# mindbrain_schematic_v2.net
KiCad netlist of a schematic drawn in EAGLE
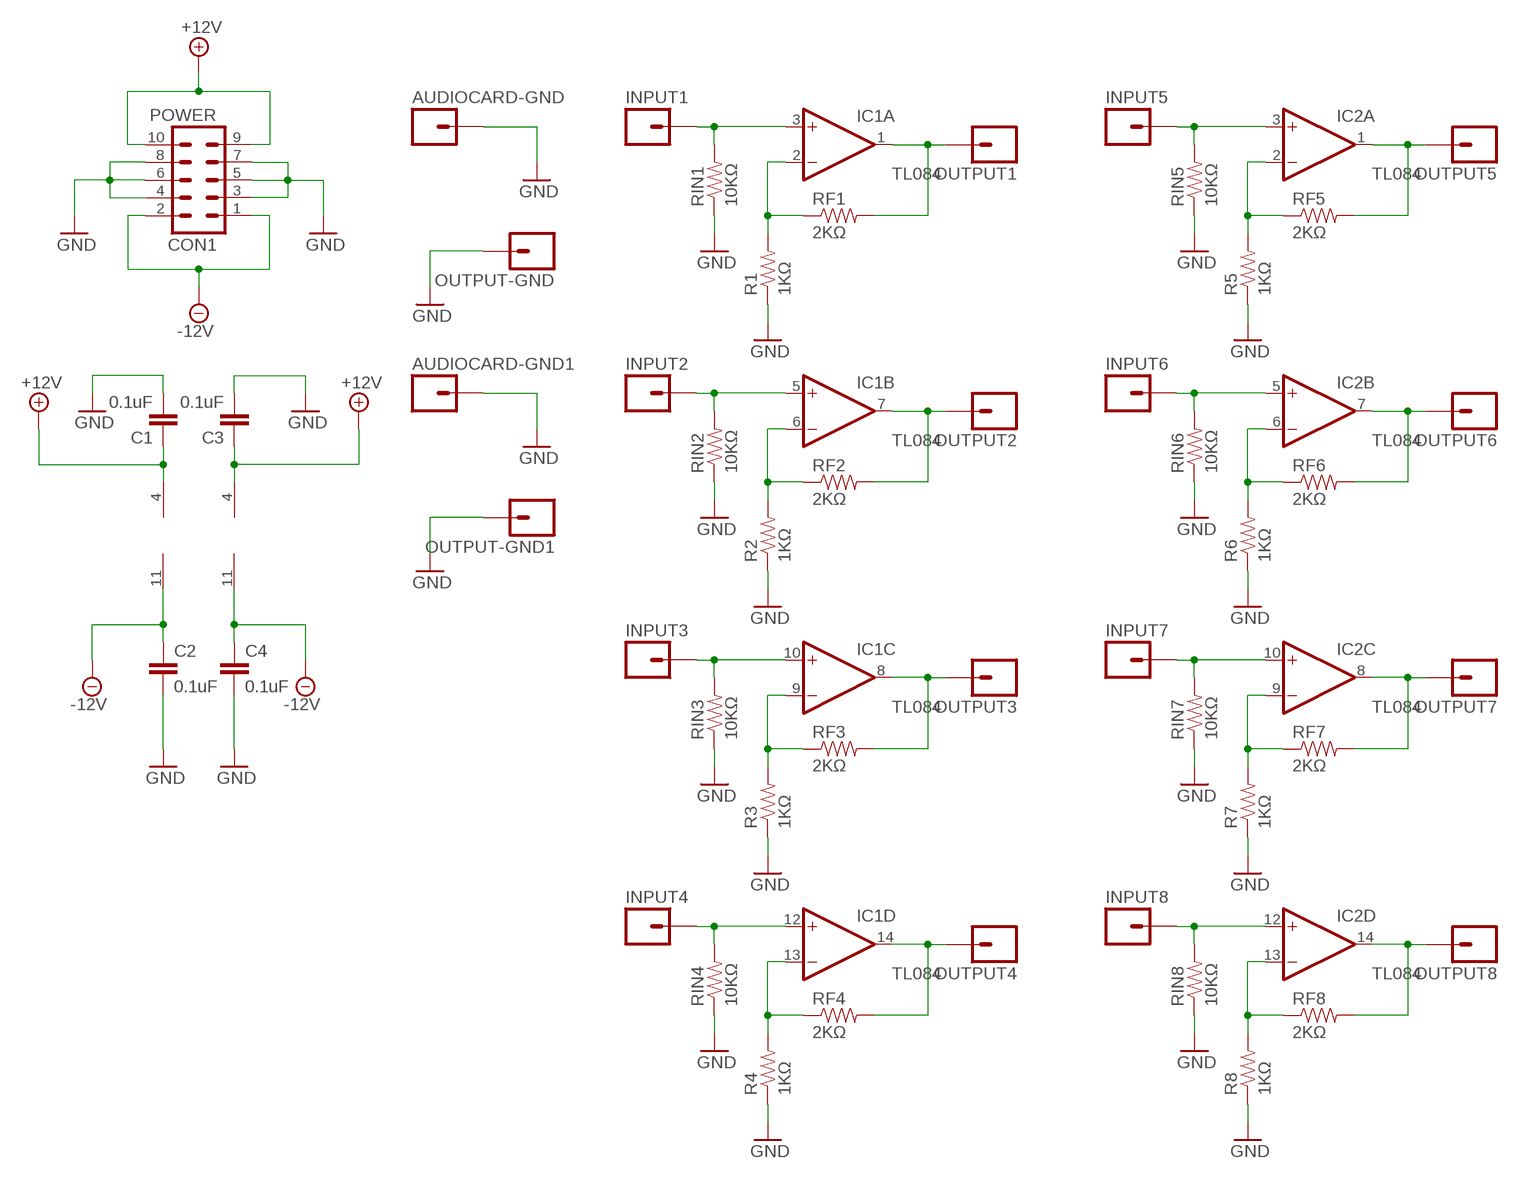
[diagram p0: schematic, sheet 1]

(export (version "E")
  (design (tool "Eeschema 10.0.6"))
  (components
    (comp (ref "AUDIOCARD-GND")
      (value "M01NOSILK-KIT")
      (footprint "eagle-import:1X01NS-KIT")
      (libsource (lib "eagle-import") (part "M01NOSILK-KIT"))
    )
    (comp (ref "AUDIOCARD-GND1")
      (value "M01NOSILK-KIT")
      (footprint "eagle-import:1X01NS-KIT")
      (libsource (lib "eagle-import") (part "M01NOSILK-KIT"))
    )
    (comp (ref "C1")
      (value "0.1uF")
      (footprint "eagle-import:CAP-PTH-SMALL-KIT")
      (libsource (lib "eagle-import") (part "CAPKIT"))
    )
    (comp (ref "C2")
      (value "0.1uF")
      (footprint "eagle-import:CAP-PTH-SMALL-KIT")
      (libsource (lib "eagle-import") (part "CAPKIT"))
    )
    (comp (ref "C3")
      (value "0.1uF")
      (footprint "eagle-import:CAP-PTH-SMALL-KIT")
      (libsource (lib "eagle-import") (part "CAPKIT"))
    )
    (comp (ref "C4")
      (value "0.1uF")
      (footprint "eagle-import:CAP-PTH-SMALL-KIT")
      (libsource (lib "eagle-import") (part "CAPKIT"))
    )
    (comp (ref "CON1")
      (value "POWER")
      (footprint "eagle-import:2X5-SHROUDED")
      (libsource (lib "eagle-import") (part "M05X2SHD"))
    )
    (comp (ref "IC1")
      (value "TL084")
      (footprint "eagle-import:DIL14")
      (libsource (lib "eagle-import") (part "TL084P"))
    )
    (comp (ref "IC2")
      (value "TL084")
      (footprint "eagle-import:DIL14")
      (libsource (lib "eagle-import") (part "TL084P"))
    )
    (comp (ref "INPUT1")
      (value "M01NOSILK-KIT")
      (footprint "eagle-import:1X01NS-KIT")
      (libsource (lib "eagle-import") (part "M01NOSILK-KIT"))
    )
    (comp (ref "INPUT2")
      (value "M01NOSILK-KIT")
      (footprint "eagle-import:1X01NS-KIT")
      (libsource (lib "eagle-import") (part "M01NOSILK-KIT"))
    )
    (comp (ref "INPUT3")
      (value "M01NOSILK-KIT")
      (footprint "eagle-import:1X01NS-KIT")
      (libsource (lib "eagle-import") (part "M01NOSILK-KIT"))
    )
    (comp (ref "INPUT4")
      (value "M01NOSILK-KIT")
      (footprint "eagle-import:1X01NS-KIT")
      (libsource (lib "eagle-import") (part "M01NOSILK-KIT"))
    )
    (comp (ref "INPUT5")
      (value "M01NOSILK-KIT")
      (footprint "eagle-import:1X01NS-KIT")
      (libsource (lib "eagle-import") (part "M01NOSILK-KIT"))
    )
    (comp (ref "INPUT6")
      (value "M01NOSILK-KIT")
      (footprint "eagle-import:1X01NS-KIT")
      (libsource (lib "eagle-import") (part "M01NOSILK-KIT"))
    )
    (comp (ref "INPUT7")
      (value "M01NOSILK-KIT")
      (footprint "eagle-import:1X01NS-KIT")
      (libsource (lib "eagle-import") (part "M01NOSILK-KIT"))
    )
    (comp (ref "INPUT8")
      (value "M01NOSILK-KIT")
      (footprint "eagle-import:1X01NS-KIT")
      (libsource (lib "eagle-import") (part "M01NOSILK-KIT"))
    )
    (comp (ref "OUTPUT-GND")
      (value "M01NOSILK-KIT")
      (footprint "eagle-import:1X01NS-KIT")
      (libsource (lib "eagle-import") (part "M01NOSILK-KIT"))
    )
    (comp (ref "OUTPUT-GND1")
      (value "M01NOSILK-KIT")
      (footprint "eagle-import:1X01NS-KIT")
      (libsource (lib "eagle-import") (part "M01NOSILK-KIT"))
    )
    (comp (ref "OUTPUT1")
      (value "M01NOSILK-KIT")
      (footprint "eagle-import:1X01NS-KIT")
      (libsource (lib "eagle-import") (part "M01NOSILK-KIT"))
    )
    (comp (ref "OUTPUT2")
      (value "M01NOSILK-KIT")
      (footprint "eagle-import:1X01NS-KIT")
      (libsource (lib "eagle-import") (part "M01NOSILK-KIT"))
    )
    (comp (ref "OUTPUT3")
      (value "M01NOSILK-KIT")
      (footprint "eagle-import:1X01NS-KIT")
      (libsource (lib "eagle-import") (part "M01NOSILK-KIT"))
    )
    (comp (ref "OUTPUT4")
      (value "M01NOSILK-KIT")
      (footprint "eagle-import:1X01NS-KIT")
      (libsource (lib "eagle-import") (part "M01NOSILK-KIT"))
    )
    (comp (ref "OUTPUT5")
      (value "M01NOSILK-KIT")
      (footprint "eagle-import:1X01NS-KIT")
      (libsource (lib "eagle-import") (part "M01NOSILK-KIT"))
    )
    (comp (ref "OUTPUT6")
      (value "M01NOSILK-KIT")
      (footprint "eagle-import:1X01NS-KIT")
      (libsource (lib "eagle-import") (part "M01NOSILK-KIT"))
    )
    (comp (ref "OUTPUT7")
      (value "M01NOSILK-KIT")
      (footprint "eagle-import:1X01NS-KIT")
      (libsource (lib "eagle-import") (part "M01NOSILK-KIT"))
    )
    (comp (ref "OUTPUT8")
      (value "M01NOSILK-KIT")
      (footprint "eagle-import:1X01NS-KIT")
      (libsource (lib "eagle-import") (part "M01NOSILK-KIT"))
    )
    (comp (ref "R1")
      (value "1KΩ")
      (footprint "eagle-import:AXIAL-0.4")
      (libsource (lib "eagle-import") (part "RESISTORPTH-1/4W"))
    )
    (comp (ref "R2")
      (value "1KΩ")
      (footprint "eagle-import:AXIAL-0.4")
      (libsource (lib "eagle-import") (part "RESISTORPTH-1/4W"))
    )
    (comp (ref "R3")
      (value "1KΩ")
      (footprint "eagle-import:AXIAL-0.4")
      (libsource (lib "eagle-import") (part "RESISTORPTH-1/4W"))
    )
    (comp (ref "R4")
      (value "1KΩ")
      (footprint "eagle-import:AXIAL-0.4")
      (libsource (lib "eagle-import") (part "RESISTORPTH-1/4W"))
    )
    (comp (ref "R5")
      (value "1KΩ")
      (footprint "eagle-import:AXIAL-0.4")
      (libsource (lib "eagle-import") (part "RESISTORPTH-1/4W"))
    )
    (comp (ref "R6")
      (value "1KΩ")
      (footprint "eagle-import:AXIAL-0.4")
      (libsource (lib "eagle-import") (part "RESISTORPTH-1/4W"))
    )
    (comp (ref "R7")
      (value "1KΩ")
      (footprint "eagle-import:AXIAL-0.4")
      (libsource (lib "eagle-import") (part "RESISTORPTH-1/4W"))
    )
    (comp (ref "R8")
      (value "1KΩ")
      (footprint "eagle-import:AXIAL-0.4")
      (libsource (lib "eagle-import") (part "RESISTORPTH-1/4W"))
    )
    (comp (ref "RF1")
      (value "2KΩ")
      (footprint "eagle-import:AXIAL-0.4")
      (libsource (lib "eagle-import") (part "RESISTORPTH-1/4W"))
    )
    (comp (ref "RF2")
      (value "2KΩ")
      (footprint "eagle-import:AXIAL-0.4")
      (libsource (lib "eagle-import") (part "RESISTORPTH-1/4W"))
    )
    (comp (ref "RF3")
      (value "2KΩ")
      (footprint "eagle-import:AXIAL-0.4")
      (libsource (lib "eagle-import") (part "RESISTORPTH-1/4W"))
    )
    (comp (ref "RF4")
      (value "2KΩ")
      (footprint "eagle-import:AXIAL-0.4")
      (libsource (lib "eagle-import") (part "RESISTORPTH-1/4W"))
    )
    (comp (ref "RF5")
      (value "2KΩ")
      (footprint "eagle-import:AXIAL-0.4")
      (libsource (lib "eagle-import") (part "RESISTORPTH-1/4W"))
    )
    (comp (ref "RF6")
      (value "2KΩ")
      (footprint "eagle-import:AXIAL-0.4")
      (libsource (lib "eagle-import") (part "RESISTORPTH-1/4W"))
    )
    (comp (ref "RF7")
      (value "2KΩ")
      (footprint "eagle-import:AXIAL-0.4")
      (libsource (lib "eagle-import") (part "RESISTORPTH-1/4W"))
    )
    (comp (ref "RF8")
      (value "2KΩ")
      (footprint "eagle-import:AXIAL-0.4")
      (libsource (lib "eagle-import") (part "RESISTORPTH-1/4W"))
    )
    (comp (ref "RIN1")
      (value "10KΩ")
      (footprint "eagle-import:AXIAL-0.4")
      (libsource (lib "eagle-import") (part "RESISTORPTH-1/4W"))
    )
    (comp (ref "RIN2")
      (value "10KΩ")
      (footprint "eagle-import:AXIAL-0.4")
      (libsource (lib "eagle-import") (part "RESISTORPTH-1/4W"))
    )
    (comp (ref "RIN3")
      (value "10KΩ")
      (footprint "eagle-import:AXIAL-0.4")
      (libsource (lib "eagle-import") (part "RESISTORPTH-1/4W"))
    )
    (comp (ref "RIN4")
      (value "10KΩ")
      (footprint "eagle-import:AXIAL-0.4")
      (libsource (lib "eagle-import") (part "RESISTORPTH-1/4W"))
    )
    (comp (ref "RIN5")
      (value "10KΩ")
      (footprint "eagle-import:AXIAL-0.4")
      (libsource (lib "eagle-import") (part "RESISTORPTH-1/4W"))
    )
    (comp (ref "RIN6")
      (value "10KΩ")
      (footprint "eagle-import:AXIAL-0.4")
      (libsource (lib "eagle-import") (part "RESISTORPTH-1/4W"))
    )
    (comp (ref "RIN7")
      (value "10KΩ")
      (footprint "eagle-import:AXIAL-0.4")
      (libsource (lib "eagle-import") (part "RESISTORPTH-1/4W"))
    )
    (comp (ref "RIN8")
      (value "10KΩ")
      (footprint "eagle-import:AXIAL-0.4")
      (libsource (lib "eagle-import") (part "RESISTORPTH-1/4W"))
    )
  )
  (nets
    (net (code "1") (name "+12V") (class "Default")
      (node (ref "C1") (pin "1") (pinfunction "1_1") (pintype "passive"))
      (node (ref "C3") (pin "1") (pinfunction "1_1") (pintype "passive"))
      (node (ref "CON1") (pin "10") (pinfunction "10_10") (pintype "passive"))
      (node (ref "CON1") (pin "9") (pinfunction "9_9") (pintype "passive"))
      (node (ref "IC1") (pin "4") (pinfunction "V+_4") (pintype "power_in"))
      (node (ref "IC2") (pin "4") (pinfunction "V+_4") (pintype "power_in"))
    )
    (net (code "2") (name "-12V") (class "Default")
      (node (ref "C2") (pin "1") (pinfunction "1_1") (pintype "passive"))
      (node (ref "C4") (pin "1") (pinfunction "1_1") (pintype "passive"))
      (node (ref "CON1") (pin "1") (pinfunction "1_1") (pintype "passive"))
      (node (ref "CON1") (pin "2") (pinfunction "2_2") (pintype "passive"))
      (node (ref "IC1") (pin "11") (pinfunction "V-_11") (pintype "power_in"))
      (node (ref "IC2") (pin "11") (pinfunction "V-_11") (pintype "power_in"))
    )
    (net (code "3") (name "GND") (class "Default")
      (node (ref "AUDIOCARD-GND") (pin "1") (pinfunction "1_1") (pintype "passive"))
      (node (ref "AUDIOCARD-GND1") (pin "1") (pinfunction "1_1") (pintype "passive"))
      (node (ref "C1") (pin "2") (pinfunction "2_2") (pintype "passive"))
      (node (ref "C2") (pin "2") (pinfunction "2_2") (pintype "passive"))
      (node (ref "C3") (pin "2") (pinfunction "2_2") (pintype "passive"))
      (node (ref "C4") (pin "2") (pinfunction "2_2") (pintype "passive"))
      (node (ref "CON1") (pin "3") (pinfunction "3_3") (pintype "passive"))
      (node (ref "CON1") (pin "4") (pinfunction "4_4") (pintype "passive"))
      (node (ref "CON1") (pin "5") (pinfunction "5_5") (pintype "passive"))
      (node (ref "CON1") (pin "6") (pinfunction "6_6") (pintype "passive"))
      (node (ref "CON1") (pin "7") (pinfunction "7_7") (pintype "passive"))
      (node (ref "CON1") (pin "8") (pinfunction "8_8") (pintype "passive"))
      (node (ref "OUTPUT-GND") (pin "1") (pinfunction "1_1") (pintype "passive"))
      (node (ref "OUTPUT-GND1") (pin "1") (pinfunction "1_1") (pintype "passive"))
      (node (ref "R1") (pin "P$1") (pinfunction "1_P$1") (pintype "passive"))
      (node (ref "R2") (pin "P$1") (pinfunction "1_P$1") (pintype "passive"))
      (node (ref "R3") (pin "P$1") (pinfunction "1_P$1") (pintype "passive"))
      (node (ref "R4") (pin "P$1") (pinfunction "1_P$1") (pintype "passive"))
      (node (ref "R5") (pin "P$1") (pinfunction "1_P$1") (pintype "passive"))
      (node (ref "R6") (pin "P$1") (pinfunction "1_P$1") (pintype "passive"))
      (node (ref "R7") (pin "P$1") (pinfunction "1_P$1") (pintype "passive"))
      (node (ref "R8") (pin "P$1") (pinfunction "1_P$1") (pintype "passive"))
      (node (ref "RIN1") (pin "P$1") (pinfunction "1_P$1") (pintype "passive"))
      (node (ref "RIN2") (pin "P$1") (pinfunction "1_P$1") (pintype "passive"))
      (node (ref "RIN3") (pin "P$1") (pinfunction "1_P$1") (pintype "passive"))
      (node (ref "RIN4") (pin "P$1") (pinfunction "1_P$1") (pintype "passive"))
      (node (ref "RIN5") (pin "P$1") (pinfunction "1_P$1") (pintype "passive"))
      (node (ref "RIN6") (pin "P$1") (pinfunction "1_P$1") (pintype "passive"))
      (node (ref "RIN7") (pin "P$1") (pinfunction "1_P$1") (pintype "passive"))
      (node (ref "RIN8") (pin "P$1") (pinfunction "1_P$1") (pintype "passive"))
    )
    (net (code "4") (name "Net-(IC1A-+IN)") (class "Default")
      (node (ref "IC1") (pin "3") (pinfunction "+IN_3") (pintype "input"))
      (node (ref "INPUT1") (pin "1") (pinfunction "1_1") (pintype "passive"))
      (node (ref "RIN1") (pin "P$2") (pinfunction "2_P$2") (pintype "passive"))
    )
    (net (code "5") (name "Net-(IC1A--IN)") (class "Default")
      (node (ref "IC1") (pin "2") (pinfunction "-IN_2") (pintype "input"))
      (node (ref "R1") (pin "P$2") (pinfunction "2_P$2") (pintype "passive"))
      (node (ref "RF1") (pin "P$1") (pinfunction "1_P$1") (pintype "passive"))
    )
    (net (code "6") (name "Net-(IC1A-OUT)") (class "Default")
      (node (ref "IC1") (pin "1") (pinfunction "OUT_1") (pintype "output"))
      (node (ref "OUTPUT1") (pin "1") (pinfunction "1_1") (pintype "passive"))
      (node (ref "RF1") (pin "P$2") (pinfunction "2_P$2") (pintype "passive"))
    )
    (net (code "7") (name "Net-(IC1B-+IN)") (class "Default")
      (node (ref "IC1") (pin "5") (pinfunction "+IN_5") (pintype "input"))
      (node (ref "INPUT2") (pin "1") (pinfunction "1_1") (pintype "passive"))
      (node (ref "RIN2") (pin "P$2") (pinfunction "2_P$2") (pintype "passive"))
    )
    (net (code "8") (name "Net-(IC1B--IN)") (class "Default")
      (node (ref "IC1") (pin "6") (pinfunction "-IN_6") (pintype "input"))
      (node (ref "R2") (pin "P$2") (pinfunction "2_P$2") (pintype "passive"))
      (node (ref "RF2") (pin "P$1") (pinfunction "1_P$1") (pintype "passive"))
    )
    (net (code "9") (name "Net-(IC1B-OUT)") (class "Default")
      (node (ref "IC1") (pin "7") (pinfunction "OUT_7") (pintype "output"))
      (node (ref "OUTPUT2") (pin "1") (pinfunction "1_1") (pintype "passive"))
      (node (ref "RF2") (pin "P$2") (pinfunction "2_P$2") (pintype "passive"))
    )
    (net (code "10") (name "Net-(IC1C-+IN)") (class "Default")
      (node (ref "IC1") (pin "10") (pinfunction "+IN_10") (pintype "input"))
      (node (ref "INPUT3") (pin "1") (pinfunction "1_1") (pintype "passive"))
      (node (ref "RIN3") (pin "P$2") (pinfunction "2_P$2") (pintype "passive"))
    )
    (net (code "11") (name "Net-(IC1C--IN)") (class "Default")
      (node (ref "IC1") (pin "9") (pinfunction "-IN_9") (pintype "input"))
      (node (ref "R3") (pin "P$2") (pinfunction "2_P$2") (pintype "passive"))
      (node (ref "RF3") (pin "P$1") (pinfunction "1_P$1") (pintype "passive"))
    )
    (net (code "12") (name "Net-(IC1C-OUT)") (class "Default")
      (node (ref "IC1") (pin "8") (pinfunction "OUT_8") (pintype "output"))
      (node (ref "OUTPUT3") (pin "1") (pinfunction "1_1") (pintype "passive"))
      (node (ref "RF3") (pin "P$2") (pinfunction "2_P$2") (pintype "passive"))
    )
    (net (code "13") (name "Net-(IC1D-+IN)") (class "Default")
      (node (ref "IC1") (pin "12") (pinfunction "+IN_12") (pintype "input"))
      (node (ref "INPUT4") (pin "1") (pinfunction "1_1") (pintype "passive"))
      (node (ref "RIN4") (pin "P$2") (pinfunction "2_P$2") (pintype "passive"))
    )
    (net (code "14") (name "Net-(IC1D--IN)") (class "Default")
      (node (ref "IC1") (pin "13") (pinfunction "-IN_13") (pintype "input"))
      (node (ref "R4") (pin "P$2") (pinfunction "2_P$2") (pintype "passive"))
      (node (ref "RF4") (pin "P$1") (pinfunction "1_P$1") (pintype "passive"))
    )
    (net (code "15") (name "Net-(IC1D-OUT)") (class "Default")
      (node (ref "IC1") (pin "14") (pinfunction "OUT_14") (pintype "output"))
      (node (ref "OUTPUT4") (pin "1") (pinfunction "1_1") (pintype "passive"))
      (node (ref "RF4") (pin "P$2") (pinfunction "2_P$2") (pintype "passive"))
    )
    (net (code "16") (name "Net-(IC2A-+IN)") (class "Default")
      (node (ref "IC2") (pin "3") (pinfunction "+IN_3") (pintype "input"))
      (node (ref "INPUT5") (pin "1") (pinfunction "1_1") (pintype "passive"))
      (node (ref "RIN5") (pin "P$2") (pinfunction "2_P$2") (pintype "passive"))
    )
    (net (code "17") (name "Net-(IC2A--IN)") (class "Default")
      (node (ref "IC2") (pin "2") (pinfunction "-IN_2") (pintype "input"))
      (node (ref "R5") (pin "P$2") (pinfunction "2_P$2") (pintype "passive"))
      (node (ref "RF5") (pin "P$1") (pinfunction "1_P$1") (pintype "passive"))
    )
    (net (code "18") (name "Net-(IC2A-OUT)") (class "Default")
      (node (ref "IC2") (pin "1") (pinfunction "OUT_1") (pintype "output"))
      (node (ref "OUTPUT5") (pin "1") (pinfunction "1_1") (pintype "passive"))
      (node (ref "RF5") (pin "P$2") (pinfunction "2_P$2") (pintype "passive"))
    )
    (net (code "19") (name "Net-(IC2B-+IN)") (class "Default")
      (node (ref "IC2") (pin "5") (pinfunction "+IN_5") (pintype "input"))
      (node (ref "INPUT6") (pin "1") (pinfunction "1_1") (pintype "passive"))
      (node (ref "RIN6") (pin "P$2") (pinfunction "2_P$2") (pintype "passive"))
    )
    (net (code "20") (name "Net-(IC2B--IN)") (class "Default")
      (node (ref "IC2") (pin "6") (pinfunction "-IN_6") (pintype "input"))
      (node (ref "R6") (pin "P$2") (pinfunction "2_P$2") (pintype "passive"))
      (node (ref "RF6") (pin "P$1") (pinfunction "1_P$1") (pintype "passive"))
    )
    (net (code "21") (name "Net-(IC2B-OUT)") (class "Default")
      (node (ref "IC2") (pin "7") (pinfunction "OUT_7") (pintype "output"))
      (node (ref "OUTPUT6") (pin "1") (pinfunction "1_1") (pintype "passive"))
      (node (ref "RF6") (pin "P$2") (pinfunction "2_P$2") (pintype "passive"))
    )
    (net (code "22") (name "Net-(IC2C-+IN)") (class "Default")
      (node (ref "IC2") (pin "10") (pinfunction "+IN_10") (pintype "input"))
      (node (ref "INPUT7") (pin "1") (pinfunction "1_1") (pintype "passive"))
      (node (ref "RIN7") (pin "P$2") (pinfunction "2_P$2") (pintype "passive"))
    )
    (net (code "23") (name "Net-(IC2C--IN)") (class "Default")
      (node (ref "IC2") (pin "9") (pinfunction "-IN_9") (pintype "input"))
      (node (ref "R7") (pin "P$2") (pinfunction "2_P$2") (pintype "passive"))
      (node (ref "RF7") (pin "P$1") (pinfunction "1_P$1") (pintype "passive"))
    )
    (net (code "24") (name "Net-(IC2C-OUT)") (class "Default")
      (node (ref "IC2") (pin "8") (pinfunction "OUT_8") (pintype "output"))
      (node (ref "OUTPUT7") (pin "1") (pinfunction "1_1") (pintype "passive"))
      (node (ref "RF7") (pin "P$2") (pinfunction "2_P$2") (pintype "passive"))
    )
    (net (code "25") (name "Net-(IC2D-+IN)") (class "Default")
      (node (ref "IC2") (pin "12") (pinfunction "+IN_12") (pintype "input"))
      (node (ref "INPUT8") (pin "1") (pinfunction "1_1") (pintype "passive"))
      (node (ref "RIN8") (pin "P$2") (pinfunction "2_P$2") (pintype "passive"))
    )
    (net (code "26") (name "Net-(IC2D--IN)") (class "Default")
      (node (ref "IC2") (pin "13") (pinfunction "-IN_13") (pintype "input"))
      (node (ref "R8") (pin "P$2") (pinfunction "2_P$2") (pintype "passive"))
      (node (ref "RF8") (pin "P$1") (pinfunction "1_P$1") (pintype "passive"))
    )
    (net (code "27") (name "Net-(IC2D-OUT)") (class "Default")
      (node (ref "IC2") (pin "14") (pinfunction "OUT_14") (pintype "output"))
      (node (ref "OUTPUT8") (pin "1") (pinfunction "1_1") (pintype "passive"))
      (node (ref "RF8") (pin "P$2") (pinfunction "2_P$2") (pintype "passive"))
    )
  )
)
